# Schematik_rangkaian.net
KiCad netlist of a schematic drawn in Altium Designer
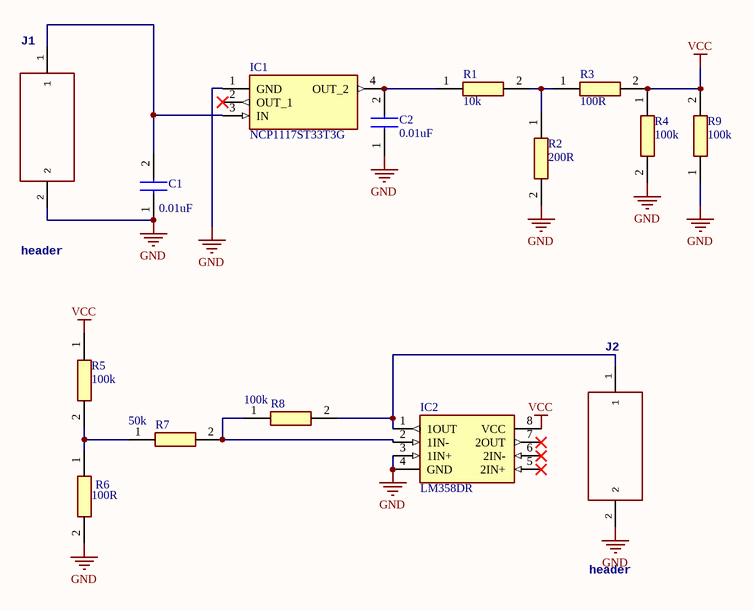
[diagram p0: Schematik_rangkaian.SchDoc]

(export (version "E")
  (design (tool "Eeschema 10.0.6"))
  (components
    (comp (ref "C1")
      (value "0.01uF")
      (footprint "SamacSys:0805_CAP_STD")
      (description "Capacitor")
      (fields
        (field (name "MANUFACTURER_PART_NUMBER") "08055A130JAQ2A")
        (field (name "MOUSER PART NUMBER") "581-08055A130JAQ2A")
      )
      (libsource (lib "SamacSys") (part "08055A130JAQ2A"))
    )
    (comp (ref "C2")
      (value "0.01uF")
      (footprint "SamacSys:0805_CAP_STD")
      (description "Capacitor")
      (fields
        (field (name "MANUFACTURER_PART_NUMBER") "08055A130JAQ2A")
        (field (name "MOUSER PART NUMBER") "581-08055A130JAQ2A")
      )
      (libsource (lib "SamacSys") (part "08055A130JAQ2A"))
    )
    (comp (ref "IC1")
      (value "NCP1117ST33T3G")
      (footprint "SamacSys:SOT230P700X180-4N")
      (description "Integrated Circuit")
      (fields
        (field (name "MOUSER PART NUMBER") "863-NCP1117ST33T3G")
        (field (name "RS PART NUMBER") "7857207P")
      )
      (libsource (lib "SamacSys") (part "NCP1117ST33T3G"))
    )
    (comp (ref "IC2")
      (value "LM358DR")
      (footprint "SamacSys:SOIC127P600X175-8N")
      (description "Integrated Circuit")
      (fields (field (name "MOUSER PART NUMBER") "595-LM358DR") (field (name "RS PART NUMBER") "0527154"))
      (libsource (lib "SamacSys") (part "LM358DR"))
    )
    (comp (ref "J1")
      (value "header")
      (footprint "SAMTEC-TMM-101-05-X-D")
      (libsource (lib "SAMTEC-TMM-101-05-X-D") (part "SAMTEC-TMM-101-05-X-DJ"))
    )
    (comp (ref "J2")
      (value "header")
      (footprint "SAMTEC-TMM-101-05-X-D")
      (libsource (lib "SAMTEC-TMM-101-05-X-D") (part "SAMTEC-TMM-101-05-X-DJ"))
    )
    (comp (ref "R1")
      (value "10k")
      (footprint "SamacSys:RESC2012X65N")
      (description "Resistor")
      (fields
        (field (name "MANUFACTURER_PART_NUMBER") "CPF0805B100KE")
        (field (name "MOUSER PART NUMBER") "279-CPF0805B100KE")
      )
      (libsource (lib "") (part "CPF0805B100KE_2"))
    )
    (comp (ref "R2")
      (value "200R")
      (footprint "SamacSys:RESC2012X65N")
      (description "Resistor")
      (fields
        (field (name "MANUFACTURER_PART_NUMBER") "CPF0805B100KE")
        (field (name "MOUSER PART NUMBER") "279-CPF0805B100KE")
      )
      (libsource (lib "") (part "CPF0805B100KE_1"))
    )
    (comp (ref "R3")
      (value "100R")
      (footprint "SamacSys:RESC2012X65N")
      (description "Resistor")
      (fields
        (field (name "MANUFACTURER_PART_NUMBER") "CPF0805B100KE")
        (field (name "MOUSER PART NUMBER") "279-CPF0805B100KE")
      )
      (libsource (lib "") (part "CPF0805B100KE_2"))
    )
    (comp (ref "R4")
      (value "100k")
      (footprint "SamacSys:RESC2012X65N")
      (description "Resistor")
      (fields
        (field (name "MANUFACTURER_PART_NUMBER") "CPF0805B100KE")
        (field (name "MOUSER PART NUMBER") "279-CPF0805B100KE")
      )
      (libsource (lib "") (part "CPF0805B100KE_1"))
    )
    (comp (ref "R5")
      (value "100k")
      (footprint "SamacSys:RESC2012X65N")
      (description "Resistor")
      (fields
        (field (name "MANUFACTURER_PART_NUMBER") "CPF0805B100KE")
        (field (name "MOUSER PART NUMBER") "279-CPF0805B100KE")
      )
      (libsource (lib "") (part "CPF0805B100KE_1"))
    )
    (comp (ref "R6")
      (value "100R")
      (footprint "SamacSys:RESC2012X65N")
      (description "Resistor")
      (fields
        (field (name "MANUFACTURER_PART_NUMBER") "CPF0805B100KE")
        (field (name "MOUSER PART NUMBER") "279-CPF0805B100KE")
      )
      (libsource (lib "") (part "CPF0805B100KE_1"))
    )
    (comp (ref "R7")
      (value "50k")
      (footprint "SamacSys:RESC2012X65N")
      (description "Resistor")
      (fields
        (field (name "MANUFACTURER_PART_NUMBER") "CPF0805B100KE")
        (field (name "MOUSER PART NUMBER") "279-CPF0805B100KE")
      )
      (libsource (lib "") (part "CPF0805B100KE_2"))
    )
    (comp (ref "R8")
      (value "100k")
      (footprint "SamacSys:RESC2012X65N")
      (description "Resistor")
      (fields
        (field (name "MANUFACTURER_PART_NUMBER") "CPF0805B100KE")
        (field (name "MOUSER PART NUMBER") "279-CPF0805B100KE")
      )
      (libsource (lib "") (part "CPF0805B100KE_2"))
    )
    (comp (ref "R9")
      (value "100k")
      (footprint "SamacSys:RESC2012X65N")
      (description "Resistor")
      (fields
        (field (name "MANUFACTURER_PART_NUMBER") "CPF0805B100KE")
        (field (name "MOUSER PART NUMBER") "279-CPF0805B100KE")
      )
      (libsource (lib "SamacSys") (part "CPF0805B100KE"))
    )
  )
  (nets
    (net (code "1") (name "GND") (class "Default")
      (node (ref "C1") (pin "1") (pinfunction "1_1") (pintype "passive"))
      (node (ref "C2") (pin "1") (pinfunction "1_1") (pintype "passive"))
      (node (ref "IC1") (pin "1") (pinfunction "GND_1") (pintype "power_in"))
      (node (ref "IC2") (pin "3") (pinfunction "1IN+_3") (pintype "input"))
      (node (ref "IC2") (pin "4") (pinfunction "GND_4") (pintype "power_in"))
      (node (ref "J1") (pin "2") (pinfunction "2_2") (pintype "passive"))
      (node (ref "J2") (pin "2") (pinfunction "2_2") (pintype "passive"))
      (node (ref "R2") (pin "2") (pinfunction "2_2") (pintype "passive"))
      (node (ref "R4") (pin "2") (pinfunction "2_2") (pintype "passive"))
      (node (ref "R6") (pin "2") (pinfunction "2_2") (pintype "passive"))
      (node (ref "R9") (pin "1") (pinfunction "1_1") (pintype "passive"))
    )
    (net (code "2") (name "Net-(IC1-IN)") (class "Default")
      (node (ref "C1") (pin "2") (pinfunction "2_2") (pintype "passive"))
      (node (ref "IC1") (pin "3") (pinfunction "IN_3") (pintype "input"))
      (node (ref "J1") (pin "1") (pinfunction "1_1") (pintype "passive"))
    )
    (net (code "3") (name "Net-(IC1-OUT_2)") (class "Default")
      (node (ref "C2") (pin "2") (pinfunction "2_2") (pintype "passive"))
      (node (ref "IC1") (pin "4") (pinfunction "OUT_2_4") (pintype "output"))
      (node (ref "R1") (pin "1") (pinfunction "1_1") (pintype "passive"))
    )
    (net (code "4") (name "Net-(IC2-1IN-)") (class "Default")
      (node (ref "IC2") (pin "2") (pinfunction "1IN-_2") (pintype "input"))
      (node (ref "R7") (pin "2") (pinfunction "2_2") (pintype "passive"))
      (node (ref "R8") (pin "1") (pinfunction "1_1") (pintype "passive"))
    )
    (net (code "5") (name "Net-(IC2-1OUT)") (class "Default")
      (node (ref "IC2") (pin "1") (pinfunction "1OUT_1") (pintype "output"))
      (node (ref "J2") (pin "1") (pinfunction "1_1") (pintype "passive"))
      (node (ref "R8") (pin "2") (pinfunction "2_2") (pintype "passive"))
    )
    (net (code "6") (name "Net-(R1-Pad2)") (class "Default")
      (node (ref "R1") (pin "2") (pinfunction "2_2") (pintype "passive"))
      (node (ref "R2") (pin "1") (pinfunction "1_1") (pintype "passive"))
      (node (ref "R3") (pin "1") (pinfunction "1_1") (pintype "passive"))
    )
    (net (code "7") (name "Net-(R5-Pad2)") (class "Default")
      (node (ref "R5") (pin "2") (pinfunction "2_2") (pintype "passive"))
      (node (ref "R6") (pin "1") (pinfunction "1_1") (pintype "passive"))
      (node (ref "R7") (pin "1") (pinfunction "1_1") (pintype "passive"))
    )
    (net (code "8") (name "VCC") (class "Default")
      (node (ref "IC2") (pin "8") (pinfunction "VCC_8") (pintype "power_in"))
      (node (ref "R3") (pin "2") (pinfunction "2_2") (pintype "passive"))
      (node (ref "R4") (pin "1") (pinfunction "1_1") (pintype "passive"))
      (node (ref "R5") (pin "1") (pinfunction "1_1") (pintype "passive"))
      (node (ref "R9") (pin "2") (pinfunction "2_2") (pintype "passive"))
    )
    (net (code "9") (name "unconnected-(IC1-OUT_1-Pad2)") (class "Default")
      (node (ref "IC1") (pin "2") (pinfunction "OUT_1_2") (pintype "output+no_connect"))
    )
    (net (code "10") (name "unconnected-(IC2-2IN+-Pad5)") (class "Default")
      (node (ref "IC2") (pin "5") (pinfunction "2IN+_5") (pintype "input+no_connect"))
    )
    (net (code "11") (name "unconnected-(IC2-2IN--Pad6)") (class "Default")
      (node (ref "IC2") (pin "6") (pinfunction "2IN-_6") (pintype "input+no_connect"))
    )
    (net (code "12") (name "unconnected-(IC2-2OUT-Pad7)") (class "Default")
      (node (ref "IC2") (pin "7") (pinfunction "2OUT_7") (pintype "output+no_connect"))
    )
  )
)
